# sx1509-breakout.net
KiCad netlist of a schematic drawn in EAGLE
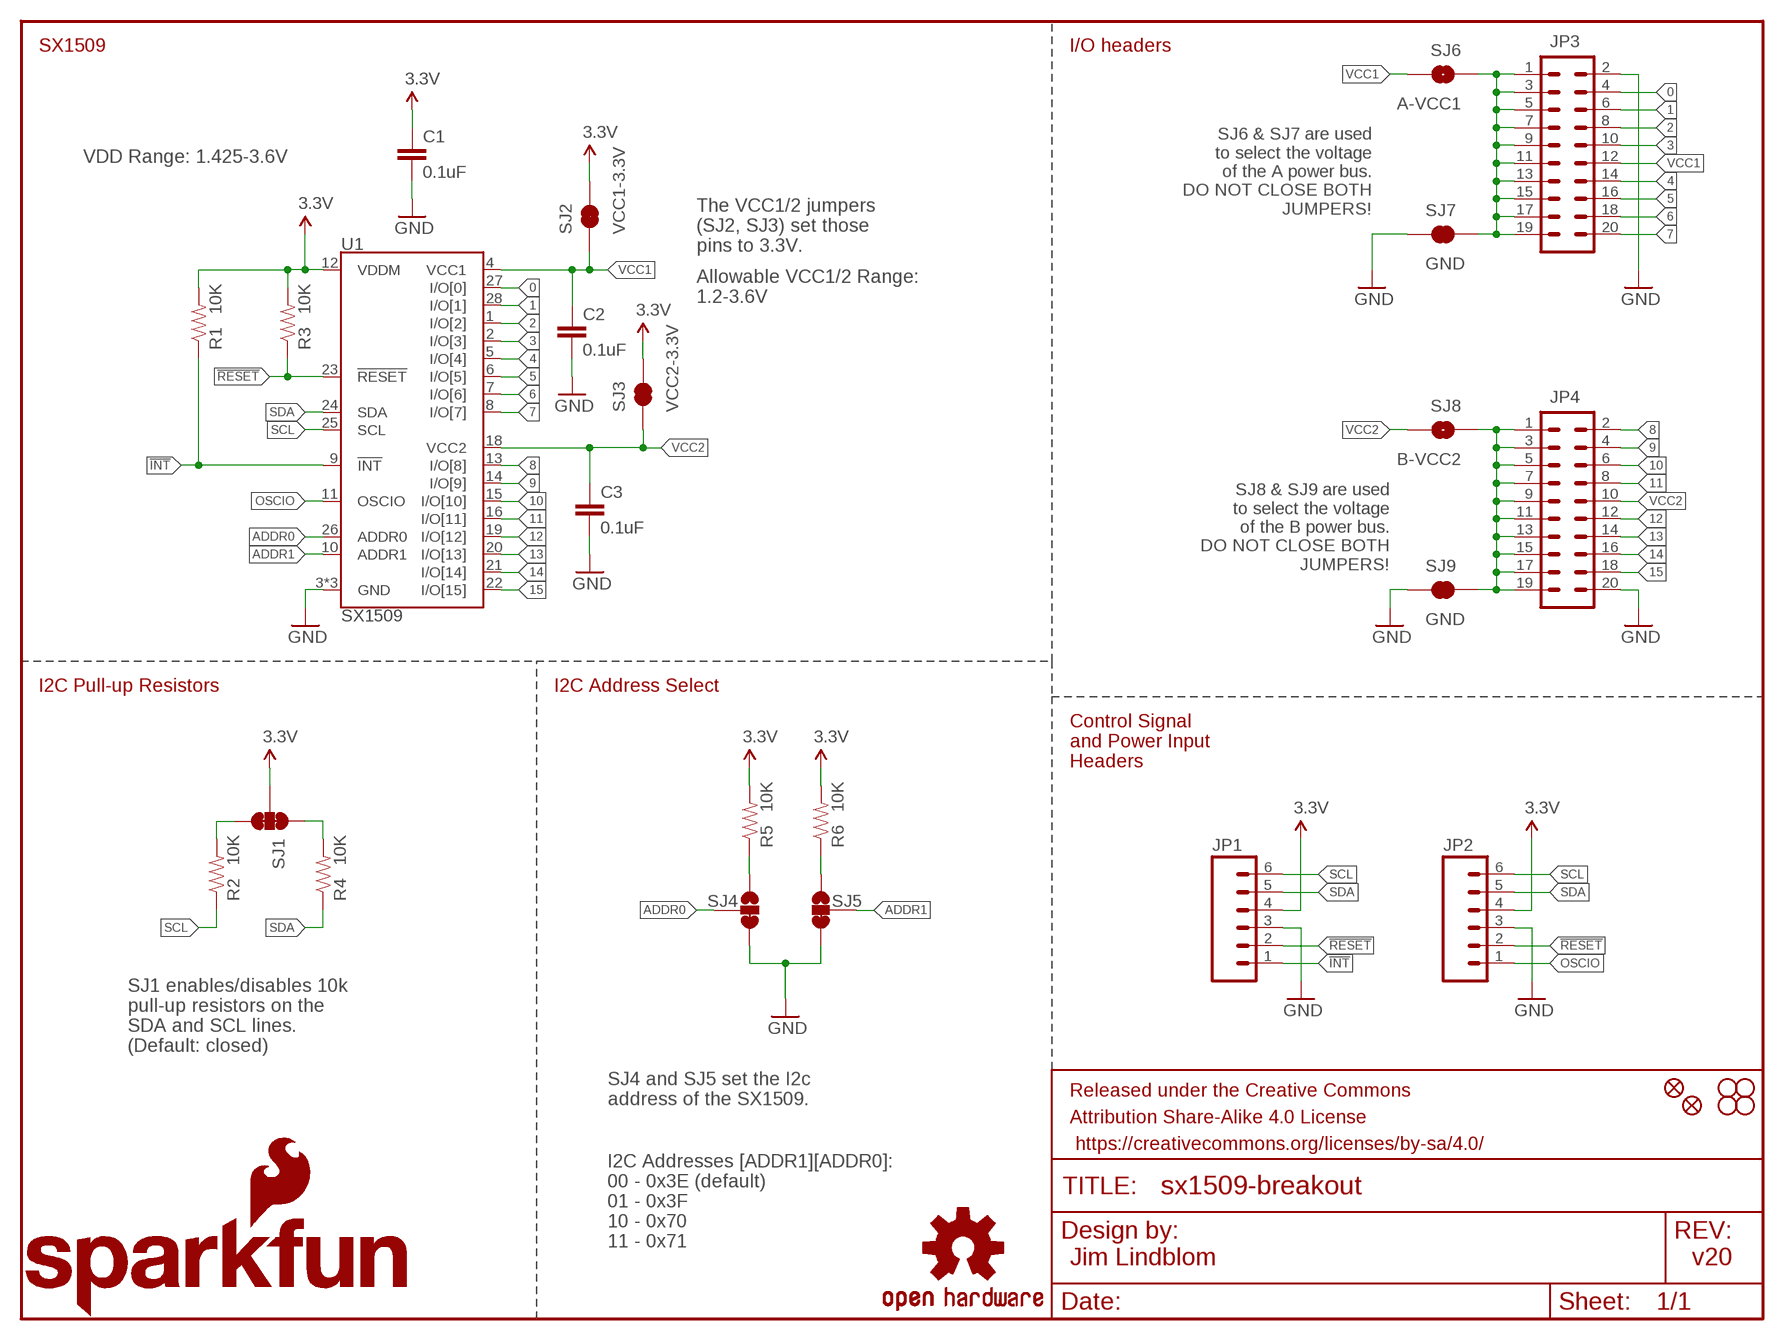
[diagram p0: schematic, sheet 1]

(export (version "E")
  (design (tool "Eeschema 10.0.6"))
  (components
    (comp (ref "C1")
      (value "0.1uF")
      (footprint "eagle-import:0603-CAP")
      (libsource (lib "eagle-import") (part "0.1UF-25V(+80/-20%)(0603)"))
    )
    (comp (ref "C2")
      (value "0.1uF")
      (footprint "eagle-import:0603-CAP")
      (libsource (lib "eagle-import") (part "0.1UF-25V(+80/-20%)(0603)"))
    )
    (comp (ref "C3")
      (value "0.1uF")
      (footprint "eagle-import:0603-CAP")
      (libsource (lib "eagle-import") (part "0.1UF-25V(+80/-20%)(0603)"))
    )
    (comp (ref "FRAME1")
      (value "FRAME-LETTER")
      (footprint "eagle-import:CREATIVE_COMMONS")
      (fields (field (name "DESIGNER") "NAME"))
      (libsource (lib "eagle-import") (part "FRAME-LETTER"))
    )
    (comp (ref "JP1")
      (value "M06SILK_FEMALE_PTH")
      (footprint "eagle-import:1X06")
      (libsource (lib "eagle-import") (part "M06SILK_FEMALE_PTH"))
    )
    (comp (ref "JP2")
      (value "M06SILK_FEMALE_PTH")
      (footprint "eagle-import:1X06")
      (libsource (lib "eagle-import") (part "M06SILK_FEMALE_PTH"))
    )
    (comp (ref "JP3")
      (value "M10X2ROUND_NOSILK")
      (footprint "eagle-import:2X10_ROUND_NOSILK")
      (libsource (lib "eagle-import") (part "M10X2ROUND_NOSILK"))
    )
    (comp (ref "JP4")
      (value "M10X2ROUND_NOSILK")
      (footprint "eagle-import:2X10_ROUND_NOSILK")
      (libsource (lib "eagle-import") (part "M10X2ROUND_NOSILK"))
    )
    (comp (ref "JP9")
      (value "FIDUCIAL1X2")
      (footprint "eagle-import:FIDUCIAL-1X2")
      (libsource (lib "eagle-import") (part "FIDUCIAL1X2"))
    )
    (comp (ref "JP10")
      (value "FIDUCIAL1X2")
      (footprint "eagle-import:FIDUCIAL-1X2")
      (libsource (lib "eagle-import") (part "FIDUCIAL1X2"))
    )
    (comp (ref "LOGO1")
      (value "SFE_LOGO_NAME_FLAME.1_INCH")
      (footprint "eagle-import:SFE_LOGO_NAME_FLAME_.1")
      (libsource (lib "eagle-import") (part "SFE_LOGO_NAME_FLAME.1_INCH"))
    )
    (comp (ref "LOGO2")
      (value "SFE_LOGO_FLAME.1_INCH")
      (footprint "eagle-import:SFE_LOGO_FLAME_.1")
      (libsource (lib "eagle-import") (part "SFE_LOGO_FLAME.1_INCH"))
    )
    (comp (ref "LOGO3")
      (value "OSHW-LOGOS")
      (footprint "eagle-import:OSHW-LOGO-S")
      (libsource (lib "eagle-import") (part "OSHW-LOGOS"))
    )
    (comp (ref "R1")
      (value "10K")
      (footprint "eagle-import:0603-RES")
      (libsource (lib "eagle-import") (part "10KOHM-1/10W-1%(0603)0603"))
    )
    (comp (ref "R2")
      (value "10K")
      (footprint "eagle-import:0603-RES")
      (libsource (lib "eagle-import") (part "10KOHM-1/10W-1%(0603)0603"))
    )
    (comp (ref "R3")
      (value "10K")
      (footprint "eagle-import:0603-RES")
      (libsource (lib "eagle-import") (part "10KOHM-1/10W-1%(0603)0603"))
    )
    (comp (ref "R4")
      (value "10K")
      (footprint "eagle-import:0603-RES")
      (libsource (lib "eagle-import") (part "10KOHM-1/10W-1%(0603)0603"))
    )
    (comp (ref "R5")
      (value "10K")
      (footprint "eagle-import:0603-RES")
      (libsource (lib "eagle-import") (part "10KOHM-1/10W-1%(0603)0603"))
    )
    (comp (ref "R6")
      (value "10K")
      (footprint "eagle-import:0603-RES")
      (libsource (lib "eagle-import") (part "10KOHM-1/10W-1%(0603)0603"))
    )
    (comp (ref "SJ1")
      (value "JUMPER-PAD-3-NC_BY_TRACE")
      (footprint "eagle-import:PAD-JUMPER-3-3OF3_NC_BY_TRACE_YES_SILK_FULL_BOX")
      (libsource (lib "eagle-import") (part "JUMPER-PAD-3-NC_BY_TRACE"))
    )
    (comp (ref "SJ2")
      (value "VCC1-3.3V")
      (footprint "eagle-import:PAD-JUMPER-2-NC_BY_TRACE_YES_SILK")
      (libsource (lib "eagle-import") (part "JUMPER-PAD-2-NC_BY_TRACE"))
    )
    (comp (ref "SJ3")
      (value "VCC2-3.3V")
      (footprint "eagle-import:PAD-JUMPER-2-NC_BY_TRACE_YES_SILK")
      (libsource (lib "eagle-import") (part "JUMPER-PAD-2-NC_BY_TRACE"))
    )
    (comp (ref "SJ4")
      (value "JUMPER-PAD-3-2OF3_NC_BY_TRACE_SMALL")
      (footprint "eagle-import:PAD-JUMPER-3-2OF3_NC_BY_TRACE_YES_SILK_FULL_BOX")
      (libsource (lib "eagle-import") (part "JUMPER-PAD-3-2OF3_NC_BY_TRACE_SMALL"))
    )
    (comp (ref "SJ5")
      (value "JUMPER-PAD-3-2OF3_NC_BY_TRACE_SMALL")
      (footprint "eagle-import:PAD-JUMPER-3-2OF3_NC_BY_TRACE_YES_SILK_FULL_BOX")
      (libsource (lib "eagle-import") (part "JUMPER-PAD-3-2OF3_NC_BY_TRACE_SMALL"))
    )
    (comp (ref "SJ6")
      (value "A-VCC1")
      (footprint "eagle-import:PAD-JUMPER-2-NO_NO_SILK")
      (libsource (lib "eagle-import") (part "JUMPER-PAD-2-NO"))
    )
    (comp (ref "SJ7")
      (value "GND")
      (footprint "eagle-import:PAD-JUMPER-2-NC_BY_TRACE_NO_SILK")
      (libsource (lib "eagle-import") (part "JUMPER-PAD-2-NC_BY_TRACENO_SILK"))
    )
    (comp (ref "SJ8")
      (value "B-VCC2")
      (footprint "eagle-import:PAD-JUMPER-2-NO_NO_SILK")
      (libsource (lib "eagle-import") (part "JUMPER-PAD-2-NO"))
    )
    (comp (ref "SJ9")
      (value "GND")
      (footprint "eagle-import:PAD-JUMPER-2-NC_BY_TRACE_NO_SILK")
      (libsource (lib "eagle-import") (part "JUMPER-PAD-2-NC_BY_TRACENO_SILK"))
    )
    (comp (ref "STANDOFF1")
      (value "STAND-OFF")
      (footprint "eagle-import:STAND-OFF")
      (libsource (lib "eagle-import") (part "STAND-OFF"))
    )
    (comp (ref "STANDOFF2")
      (value "STAND-OFF")
      (footprint "eagle-import:STAND-OFF")
      (libsource (lib "eagle-import") (part "STAND-OFF"))
    )
    (comp (ref "STANDOFF3")
      (value "STAND-OFF")
      (footprint "eagle-import:STAND-OFF")
      (libsource (lib "eagle-import") (part "STAND-OFF"))
    )
    (comp (ref "STANDOFF4")
      (value "STAND-OFF")
      (footprint "eagle-import:STAND-OFF")
      (libsource (lib "eagle-import") (part "STAND-OFF"))
    )
    (comp (ref "U1")
      (value "SX1509")
      (footprint "eagle-import:QFN-28")
      (libsource (lib "eagle-import") (part "SX1509"))
    )
  )
  (nets
    (net (code "1") (name "/~{INT}") (class "Default")
      (node (ref "JP1") (pin "1") (pinfunction "1_1") (pintype "passive"))
      (node (ref "R1") (pin "1") (pinfunction "1_1") (pintype "passive"))
      (node (ref "U1") (pin "9") (pinfunction "~{INT}_9") (pintype "bidirectional"))
    )
    (net (code "2") (name "/~{RESET}") (class "Default")
      (node (ref "JP1") (pin "2") (pinfunction "2_2") (pintype "passive"))
      (node (ref "JP2") (pin "2") (pinfunction "2_2") (pintype "passive"))
      (node (ref "R3") (pin "1") (pinfunction "1_1") (pintype "passive"))
      (node (ref "U1") (pin "23") (pinfunction "~{RESET}_23") (pintype "bidirectional"))
    )
    (net (code "3") (name "0") (class "Default")
      (node (ref "JP3") (pin "4") (pinfunction "4_4") (pintype "passive"))
      (node (ref "U1") (pin "27") (pinfunction "I/O[0]_27") (pintype "bidirectional"))
    )
    (net (code "4") (name "1") (class "Default")
      (node (ref "JP3") (pin "6") (pinfunction "6_6") (pintype "passive"))
      (node (ref "U1") (pin "28") (pinfunction "I/O[1]_28") (pintype "bidirectional"))
    )
    (net (code "5") (name "2") (class "Default")
      (node (ref "JP3") (pin "8") (pinfunction "8_8") (pintype "passive"))
      (node (ref "U1") (pin "1") (pinfunction "I/O[2]_1") (pintype "bidirectional"))
    )
    (net (code "6") (name "3") (class "Default")
      (node (ref "JP3") (pin "10") (pinfunction "10_10") (pintype "passive"))
      (node (ref "U1") (pin "2") (pinfunction "I/O[3]_2") (pintype "bidirectional"))
    )
    (net (code "7") (name "3.3V") (class "Default")
      (node (ref "C1") (pin "1") (pinfunction "1_1") (pintype "passive"))
      (node (ref "JP1") (pin "4") (pinfunction "4_4") (pintype "passive"))
      (node (ref "JP2") (pin "4") (pinfunction "4_4") (pintype "passive"))
      (node (ref "R1") (pin "2") (pinfunction "2_2") (pintype "passive"))
      (node (ref "R3") (pin "2") (pinfunction "2_2") (pintype "passive"))
      (node (ref "R5") (pin "2") (pinfunction "2_2") (pintype "passive"))
      (node (ref "R6") (pin "2") (pinfunction "2_2") (pintype "passive"))
      (node (ref "SJ1") (pin "2") (pinfunction "2_2") (pintype "passive"))
      (node (ref "SJ2") (pin "2") (pinfunction "2_2") (pintype "passive"))
      (node (ref "SJ3") (pin "2") (pinfunction "2_2") (pintype "passive"))
      (node (ref "U1") (pin "12") (pinfunction "VDDM_12") (pintype "bidirectional"))
    )
    (net (code "8") (name "4") (class "Default")
      (node (ref "JP3") (pin "14") (pinfunction "14_14") (pintype "passive"))
      (node (ref "U1") (pin "5") (pinfunction "I/O[4]_5") (pintype "bidirectional"))
    )
    (net (code "9") (name "5") (class "Default")
      (node (ref "JP3") (pin "16") (pinfunction "16_16") (pintype "passive"))
      (node (ref "U1") (pin "6") (pinfunction "I/O[5]_6") (pintype "bidirectional"))
    )
    (net (code "10") (name "6") (class "Default")
      (node (ref "JP3") (pin "18") (pinfunction "18_18") (pintype "passive"))
      (node (ref "U1") (pin "7") (pinfunction "I/O[6]_7") (pintype "bidirectional"))
    )
    (net (code "11") (name "7") (class "Default")
      (node (ref "JP3") (pin "20") (pinfunction "20_20") (pintype "passive"))
      (node (ref "U1") (pin "8") (pinfunction "I/O[7]_8") (pintype "bidirectional"))
    )
    (net (code "12") (name "8") (class "Default")
      (node (ref "JP4") (pin "2") (pinfunction "2_2") (pintype "passive"))
      (node (ref "U1") (pin "13") (pinfunction "I/O[8]_13") (pintype "bidirectional"))
    )
    (net (code "13") (name "9") (class "Default")
      (node (ref "JP4") (pin "4") (pinfunction "4_4") (pintype "passive"))
      (node (ref "U1") (pin "14") (pinfunction "I/O[9]_14") (pintype "bidirectional"))
    )
    (net (code "14") (name "10") (class "Default")
      (node (ref "JP4") (pin "6") (pinfunction "6_6") (pintype "passive"))
      (node (ref "U1") (pin "15") (pinfunction "I/O[10]_15") (pintype "bidirectional"))
    )
    (net (code "15") (name "11") (class "Default")
      (node (ref "JP4") (pin "8") (pinfunction "8_8") (pintype "passive"))
      (node (ref "U1") (pin "16") (pinfunction "I/O[11]_16") (pintype "bidirectional"))
    )
    (net (code "16") (name "12") (class "Default")
      (node (ref "JP4") (pin "12") (pinfunction "12_12") (pintype "passive"))
      (node (ref "U1") (pin "19") (pinfunction "I/O[12]_19") (pintype "bidirectional"))
    )
    (net (code "17") (name "13") (class "Default")
      (node (ref "JP4") (pin "14") (pinfunction "14_14") (pintype "passive"))
      (node (ref "U1") (pin "20") (pinfunction "I/O[13]_20") (pintype "bidirectional"))
    )
    (net (code "18") (name "14") (class "Default")
      (node (ref "JP4") (pin "16") (pinfunction "16_16") (pintype "passive"))
      (node (ref "U1") (pin "21") (pinfunction "I/O[14]_21") (pintype "bidirectional"))
    )
    (net (code "19") (name "15") (class "Default")
      (node (ref "JP4") (pin "18") (pinfunction "18_18") (pintype "passive"))
      (node (ref "U1") (pin "22") (pinfunction "I/O[15]_22") (pintype "bidirectional"))
    )
    (net (code "20") (name "ADDR0") (class "Default")
      (node (ref "SJ4") (pin "2") (pinfunction "2_2") (pintype "passive"))
      (node (ref "U1") (pin "26") (pinfunction "ADDR0_26") (pintype "bidirectional"))
    )
    (net (code "21") (name "ADDR1") (class "Default")
      (node (ref "SJ5") (pin "2") (pinfunction "2_2") (pintype "passive"))
      (node (ref "U1") (pin "10") (pinfunction "ADDR1_10") (pintype "bidirectional"))
    )
    (net (code "22") (name "GND") (class "Default")
      (node (ref "C1") (pin "2") (pinfunction "2_2") (pintype "passive"))
      (node (ref "C2") (pin "2") (pinfunction "2_2") (pintype "passive"))
      (node (ref "C3") (pin "2") (pinfunction "2_2") (pintype "passive"))
      (node (ref "JP1") (pin "3") (pinfunction "3_3") (pintype "passive"))
      (node (ref "JP2") (pin "3") (pinfunction "3_3") (pintype "passive"))
      (node (ref "JP3") (pin "2") (pinfunction "2_2") (pintype "passive"))
      (node (ref "JP4") (pin "20") (pinfunction "20_20") (pintype "passive"))
      (node (ref "SJ4") (pin "3") (pinfunction "3_3") (pintype "passive"))
      (node (ref "SJ5") (pin "3") (pinfunction "3_3") (pintype "passive"))
      (node (ref "SJ7") (pin "1") (pinfunction "1_1") (pintype "passive"))
      (node (ref "SJ9") (pin "1") (pinfunction "1_1") (pintype "passive"))
      (node (ref "U1") (pin "17") (pinfunction "GND_17") (pintype "bidirectional"))
      (node (ref "U1") (pin "29") (pinfunction "GND_29") (pintype "bidirectional"))
      (node (ref "U1") (pin "3") (pinfunction "GND_3") (pintype "bidirectional"))
    )
    (net (code "23") (name "Net-(JP3-Pad1)") (class "Default")
      (node (ref "JP3") (pin "1") (pinfunction "1_1") (pintype "passive"))
      (node (ref "JP3") (pin "11") (pinfunction "11_11") (pintype "passive"))
      (node (ref "JP3") (pin "13") (pinfunction "13_13") (pintype "passive"))
      (node (ref "JP3") (pin "15") (pinfunction "15_15") (pintype "passive"))
      (node (ref "JP3") (pin "17") (pinfunction "17_17") (pintype "passive"))
      (node (ref "JP3") (pin "19") (pinfunction "19_19") (pintype "passive"))
      (node (ref "JP3") (pin "3") (pinfunction "3_3") (pintype "passive"))
      (node (ref "JP3") (pin "5") (pinfunction "5_5") (pintype "passive"))
      (node (ref "JP3") (pin "7") (pinfunction "7_7") (pintype "passive"))
      (node (ref "JP3") (pin "9") (pinfunction "9_9") (pintype "passive"))
      (node (ref "SJ6") (pin "1") (pinfunction "1_1") (pintype "passive"))
      (node (ref "SJ7") (pin "2") (pinfunction "2_2") (pintype "passive"))
    )
    (net (code "24") (name "Net-(JP4-Pad1)") (class "Default")
      (node (ref "JP4") (pin "1") (pinfunction "1_1") (pintype "passive"))
      (node (ref "JP4") (pin "11") (pinfunction "11_11") (pintype "passive"))
      (node (ref "JP4") (pin "13") (pinfunction "13_13") (pintype "passive"))
      (node (ref "JP4") (pin "15") (pinfunction "15_15") (pintype "passive"))
      (node (ref "JP4") (pin "17") (pinfunction "17_17") (pintype "passive"))
      (node (ref "JP4") (pin "19") (pinfunction "19_19") (pintype "passive"))
      (node (ref "JP4") (pin "3") (pinfunction "3_3") (pintype "passive"))
      (node (ref "JP4") (pin "5") (pinfunction "5_5") (pintype "passive"))
      (node (ref "JP4") (pin "7") (pinfunction "7_7") (pintype "passive"))
      (node (ref "JP4") (pin "9") (pinfunction "9_9") (pintype "passive"))
      (node (ref "SJ8") (pin "1") (pinfunction "1_1") (pintype "passive"))
      (node (ref "SJ9") (pin "2") (pinfunction "2_2") (pintype "passive"))
    )
    (net (code "25") (name "Net-(R2-Pad2)") (class "Default")
      (node (ref "R2") (pin "2") (pinfunction "2_2") (pintype "passive"))
      (node (ref "SJ1") (pin "3") (pinfunction "3_3") (pintype "passive"))
    )
    (net (code "26") (name "Net-(R4-Pad2)") (class "Default")
      (node (ref "R4") (pin "2") (pinfunction "2_2") (pintype "passive"))
      (node (ref "SJ1") (pin "1") (pinfunction "1_1") (pintype "passive"))
    )
    (net (code "27") (name "Net-(R5-Pad1)") (class "Default")
      (node (ref "R5") (pin "1") (pinfunction "1_1") (pintype "passive"))
      (node (ref "SJ4") (pin "1") (pinfunction "1_1") (pintype "passive"))
    )
    (net (code "28") (name "Net-(R6-Pad1)") (class "Default")
      (node (ref "R6") (pin "1") (pinfunction "1_1") (pintype "passive"))
      (node (ref "SJ5") (pin "1") (pinfunction "1_1") (pintype "passive"))
    )
    (net (code "29") (name "OSCIO") (class "Default")
      (node (ref "JP2") (pin "1") (pinfunction "1_1") (pintype "passive"))
      (node (ref "U1") (pin "11") (pinfunction "OSCIO_11") (pintype "bidirectional"))
    )
    (net (code "30") (name "SCL") (class "Default")
      (node (ref "JP1") (pin "6") (pinfunction "6_6") (pintype "passive"))
      (node (ref "JP2") (pin "6") (pinfunction "6_6") (pintype "passive"))
      (node (ref "R2") (pin "1") (pinfunction "1_1") (pintype "passive"))
      (node (ref "U1") (pin "25") (pinfunction "SCL_25") (pintype "bidirectional"))
    )
    (net (code "31") (name "SDA") (class "Default")
      (node (ref "JP1") (pin "5") (pinfunction "5_5") (pintype "passive"))
      (node (ref "JP2") (pin "5") (pinfunction "5_5") (pintype "passive"))
      (node (ref "R4") (pin "1") (pinfunction "1_1") (pintype "passive"))
      (node (ref "U1") (pin "24") (pinfunction "SDA_24") (pintype "bidirectional"))
    )
    (net (code "32") (name "VCC1") (class "Default")
      (node (ref "C2") (pin "1") (pinfunction "1_1") (pintype "passive"))
      (node (ref "JP3") (pin "12") (pinfunction "12_12") (pintype "passive"))
      (node (ref "SJ2") (pin "1") (pinfunction "1_1") (pintype "passive"))
      (node (ref "SJ6") (pin "2") (pinfunction "2_2") (pintype "passive"))
      (node (ref "U1") (pin "4") (pinfunction "VCC1_4") (pintype "bidirectional"))
    )
    (net (code "33") (name "VCC2") (class "Default")
      (node (ref "C3") (pin "1") (pinfunction "1_1") (pintype "passive"))
      (node (ref "JP4") (pin "10") (pinfunction "10_10") (pintype "passive"))
      (node (ref "SJ3") (pin "1") (pinfunction "1_1") (pintype "passive"))
      (node (ref "SJ8") (pin "2") (pinfunction "2_2") (pintype "passive"))
      (node (ref "U1") (pin "18") (pinfunction "VCC2_18") (pintype "bidirectional"))
    )
  )
)
